# miernik-temperatury.net
KiCad netlist of a schematic drawn in EAGLE
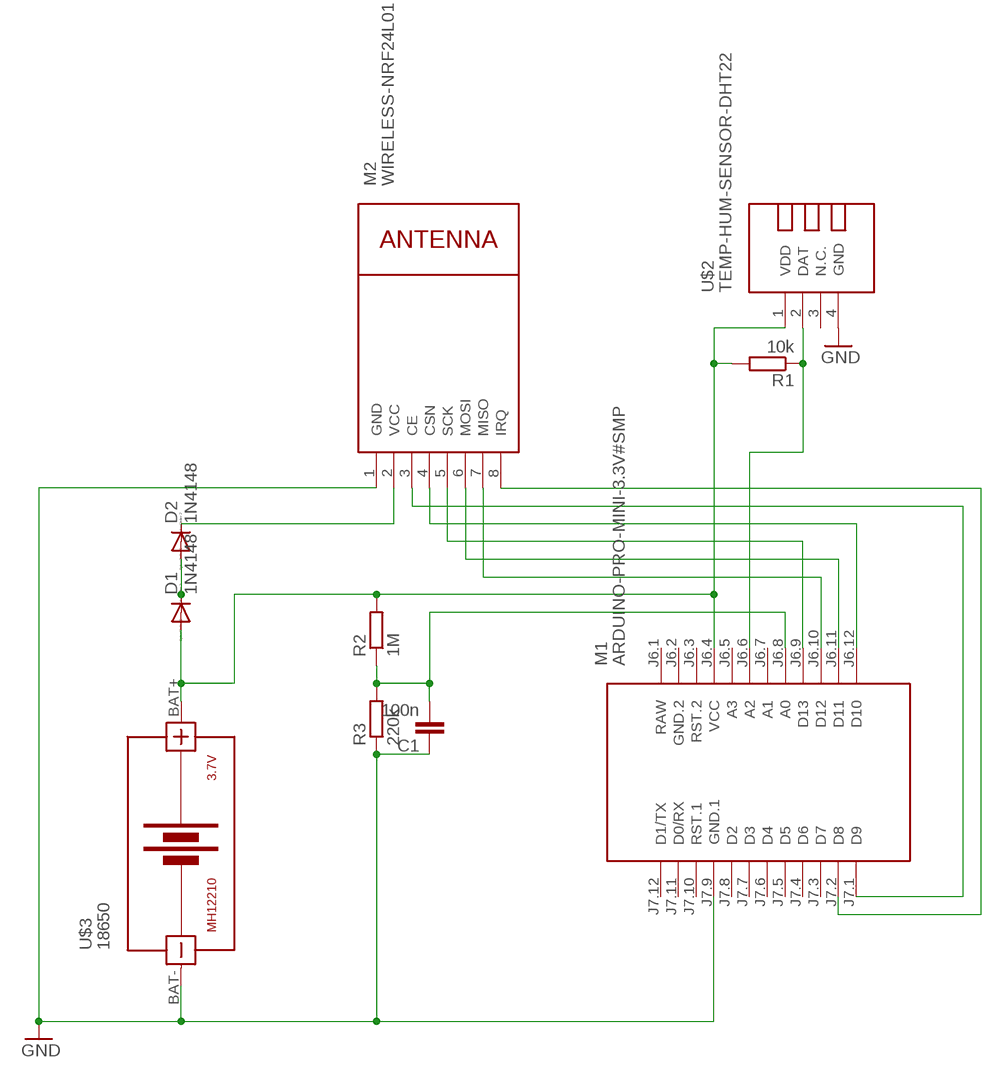
[diagram p0: schematic, sheet 1]

(export (version "E")
  (design (tool "Eeschema 10.0.6"))
  (components
    (comp (ref "C1")
      (value "100n")
      (footprint "eagle-import:C5B3")
      (libsource (lib "eagle-import") (part "C5/3"))
    )
    (comp (ref "D1")
      (value "1N4148")
      (footprint "eagle-import:DO35-10")
      (libsource (lib "eagle-import") (part "1N4148DO35-10"))
    )
    (comp (ref "D2")
      (value "1N4148")
      (footprint "eagle-import:DO35-10")
      (libsource (lib "eagle-import") (part "1N4148DO35-10"))
    )
    (comp (ref "M1")
      (value "ARDUINO-PRO-MINI-3.3V#SMP")
      (footprint "eagle-import:ARDUINO-PRO-MINI#SMP")
      (libsource (lib "eagle-import") (part "ARDUINO-PRO-MINI-#SMP3.3V"))
    )
    (comp (ref "M2")
      (value "WIRELESS-NRF24L01")
      (footprint "eagle-import:WIRELESS-NRF24L01")
      (libsource (lib "eagle-import") (part "WIRELESS-NRF24L01"))
    )
    (comp (ref "R1")
      (value "10k")
      (footprint "eagle-import:0309_12")
      (libsource (lib "eagle-import") (part "R-EU_0309/12"))
    )
    (comp (ref "R2")
      (value "1M")
      (footprint "eagle-import:0309_12")
      (libsource (lib "eagle-import") (part "R-EU_0309/12"))
    )
    (comp (ref "R3")
      (value "220k")
      (footprint "eagle-import:0309_12")
      (libsource (lib "eagle-import") (part "R-EU_0309/12"))
    )
    (comp (ref "U$2")
      (value "TEMP-HUM-SENSOR-DHT22")
      (footprint "eagle-import:TEMP-HUM-SENSOR-DHT22")
      (libsource (lib "eagle-import") (part "TEMP-HUM-SENSOR-DHT22"))
    )
    (comp (ref "U$3")
      (value "18650")
      (footprint "eagle-import:BATTERY-LI-MH12210")
      (libsource (lib "eagle-import") (part "BATTERY-LI-MH12210"))
    )
  )
  (nets
    (net (code "1") (name "/GND.2") (class "Default")
      (node (ref "M1") (pin "J6.2") (pinfunction "GND.2_J6.2") (pintype "power_in"))
    )
    (net (code "2") (name "/RAW") (class "Default")
      (node (ref "M1") (pin "J6.1") (pinfunction "RAW_J6.1") (pintype "power_in"))
    )
    (net (code "3") (name "GND") (class "Default")
      (node (ref "C1") (pin "1") (pinfunction "1_1") (pintype "passive"))
      (node (ref "M1") (pin "J7.9") (pinfunction "GND.1_J7.9") (pintype "power_in"))
      (node (ref "M2") (pin "1") (pinfunction "GND_1") (pintype "power_in"))
      (node (ref "R3") (pin "1") (pinfunction "1_1") (pintype "passive"))
      (node (ref "U$2") (pin "4") (pinfunction "GND_4") (pintype "power_in"))
      (node (ref "U$3") (pin "BAT-") (pinfunction "BAT-_BAT-") (pintype "power_in"))
    )
    (net (code "4") (name "Net-(D1-PadC)") (class "Default")
      (node (ref "D1") (pin "C") (pinfunction "C_C") (pintype "passive"))
      (node (ref "D2") (pin "A") (pinfunction "A_A") (pintype "passive"))
    )
    (net (code "5") (name "Net-(M1-A0)") (class "Default")
      (node (ref "C1") (pin "2") (pinfunction "2_2") (pintype "passive"))
      (node (ref "M1") (pin "J6.8") (pinfunction "A0_J6.8") (pintype "bidirectional"))
      (node (ref "R2") (pin "1") (pinfunction "1_1") (pintype "passive"))
      (node (ref "R3") (pin "2") (pinfunction "2_2") (pintype "passive"))
    )
    (net (code "6") (name "Net-(M1-A2)") (class "Default")
      (node (ref "M1") (pin "J6.6") (pinfunction "A2_J6.6") (pintype "bidirectional"))
      (node (ref "R1") (pin "1") (pinfunction "1_1") (pintype "passive"))
      (node (ref "U$2") (pin "2") (pinfunction "DAT_2") (pintype "bidirectional"))
    )
    (net (code "7") (name "Net-(M1-D8)") (class "Default")
      (node (ref "M1") (pin "J7.2") (pinfunction "D8_J7.2") (pintype "bidirectional"))
      (node (ref "M2") (pin "8") (pinfunction "IRQ_8") (pintype "bidirectional"))
    )
    (net (code "8") (name "Net-(M1-D9)") (class "Default")
      (node (ref "M1") (pin "J7.1") (pinfunction "D9_J7.1") (pintype "bidirectional"))
      (node (ref "M2") (pin "3") (pinfunction "CE_3") (pintype "bidirectional"))
    )
    (net (code "9") (name "Net-(M1-D10)") (class "Default")
      (node (ref "M1") (pin "J6.12") (pinfunction "D10_J6.12") (pintype "bidirectional"))
      (node (ref "M2") (pin "4") (pinfunction "CSN_4") (pintype "bidirectional"))
    )
    (net (code "10") (name "Net-(M1-D11)") (class "Default")
      (node (ref "M1") (pin "J6.11") (pinfunction "D11_J6.11") (pintype "bidirectional"))
      (node (ref "M2") (pin "6") (pinfunction "MOSI_6") (pintype "bidirectional"))
    )
    (net (code "11") (name "Net-(M1-D12)") (class "Default")
      (node (ref "M1") (pin "J6.10") (pinfunction "D12_J6.10") (pintype "bidirectional"))
      (node (ref "M2") (pin "7") (pinfunction "MISO_7") (pintype "bidirectional"))
    )
    (net (code "12") (name "Net-(M1-D13)") (class "Default")
      (node (ref "M1") (pin "J6.9") (pinfunction "D13_J6.9") (pintype "bidirectional"))
      (node (ref "M2") (pin "5") (pinfunction "SCK_5") (pintype "bidirectional"))
    )
    (net (code "13") (name "Net-(M1-VCC)") (class "Default")
      (node (ref "D1") (pin "A") (pinfunction "A_A") (pintype "passive"))
      (node (ref "M1") (pin "J6.4") (pinfunction "VCC_J6.4") (pintype "power_in"))
      (node (ref "R1") (pin "2") (pinfunction "2_2") (pintype "passive"))
      (node (ref "R2") (pin "2") (pinfunction "2_2") (pintype "passive"))
      (node (ref "U$2") (pin "1") (pinfunction "VDD_1") (pintype "power_in"))
      (node (ref "U$3") (pin "BAT+") (pinfunction "BAT+_BAT+") (pintype "power_in"))
    )
    (net (code "14") (name "Net-(M2-VCC)") (class "Default")
      (node (ref "D2") (pin "C") (pinfunction "C_C") (pintype "passive"))
      (node (ref "M2") (pin "2") (pinfunction "VCC_2") (pintype "power_in"))
    )
    (net (code "15") (name "unconnected-(M1-A1-PadJ6.7)") (class "Default")
      (node (ref "M1") (pin "J6.7") (pinfunction "A1_J6.7") (pintype "bidirectional"))
    )
    (net (code "16") (name "unconnected-(M1-A3-PadJ6.5)") (class "Default")
      (node (ref "M1") (pin "J6.5") (pinfunction "A3_J6.5") (pintype "bidirectional"))
    )
    (net (code "17") (name "unconnected-(M1-D0{slash}RX-PadJ7.11)") (class "Default")
      (node (ref "M1") (pin "J7.11") (pinfunction "D0/RX_J7.11") (pintype "bidirectional"))
    )
    (net (code "18") (name "unconnected-(M1-D1{slash}TX-PadJ7.12)") (class "Default")
      (node (ref "M1") (pin "J7.12") (pinfunction "D1/TX_J7.12") (pintype "bidirectional"))
    )
    (net (code "19") (name "unconnected-(M1-D2-PadJ7.8)") (class "Default")
      (node (ref "M1") (pin "J7.8") (pinfunction "D2_J7.8") (pintype "bidirectional"))
    )
    (net (code "20") (name "unconnected-(M1-D3-PadJ7.7)") (class "Default")
      (node (ref "M1") (pin "J7.7") (pinfunction "D3_J7.7") (pintype "bidirectional"))
    )
    (net (code "21") (name "unconnected-(M1-D4-PadJ7.6)") (class "Default")
      (node (ref "M1") (pin "J7.6") (pinfunction "D4_J7.6") (pintype "bidirectional"))
    )
    (net (code "22") (name "unconnected-(M1-D5-PadJ7.5)") (class "Default")
      (node (ref "M1") (pin "J7.5") (pinfunction "D5_J7.5") (pintype "bidirectional"))
    )
    (net (code "23") (name "unconnected-(M1-D6-PadJ7.4)") (class "Default")
      (node (ref "M1") (pin "J7.4") (pinfunction "D6_J7.4") (pintype "bidirectional"))
    )
    (net (code "24") (name "unconnected-(M1-D7-PadJ7.3)") (class "Default")
      (node (ref "M1") (pin "J7.3") (pinfunction "D7_J7.3") (pintype "bidirectional"))
    )
    (net (code "25") (name "unconnected-(M1-RST.1-PadJ7.10)") (class "Default")
      (node (ref "M1") (pin "J7.10") (pinfunction "RST.1_J7.10") (pintype "bidirectional"))
    )
    (net (code "26") (name "unconnected-(M1-RST.2-PadJ6.3)") (class "Default")
      (node (ref "M1") (pin "J6.3") (pinfunction "RST.2_J6.3") (pintype "bidirectional"))
    )
    (net (code "27") (name "unconnected-(U$2-N.C.-Pad3)") (class "Default")
      (node (ref "U$2") (pin "3") (pinfunction "N.C._3") (pintype "passive"))
    )
  )
)
